# 1_1_0_Interface_board.net
KiCad netlist of a schematic drawn in Altium Designer
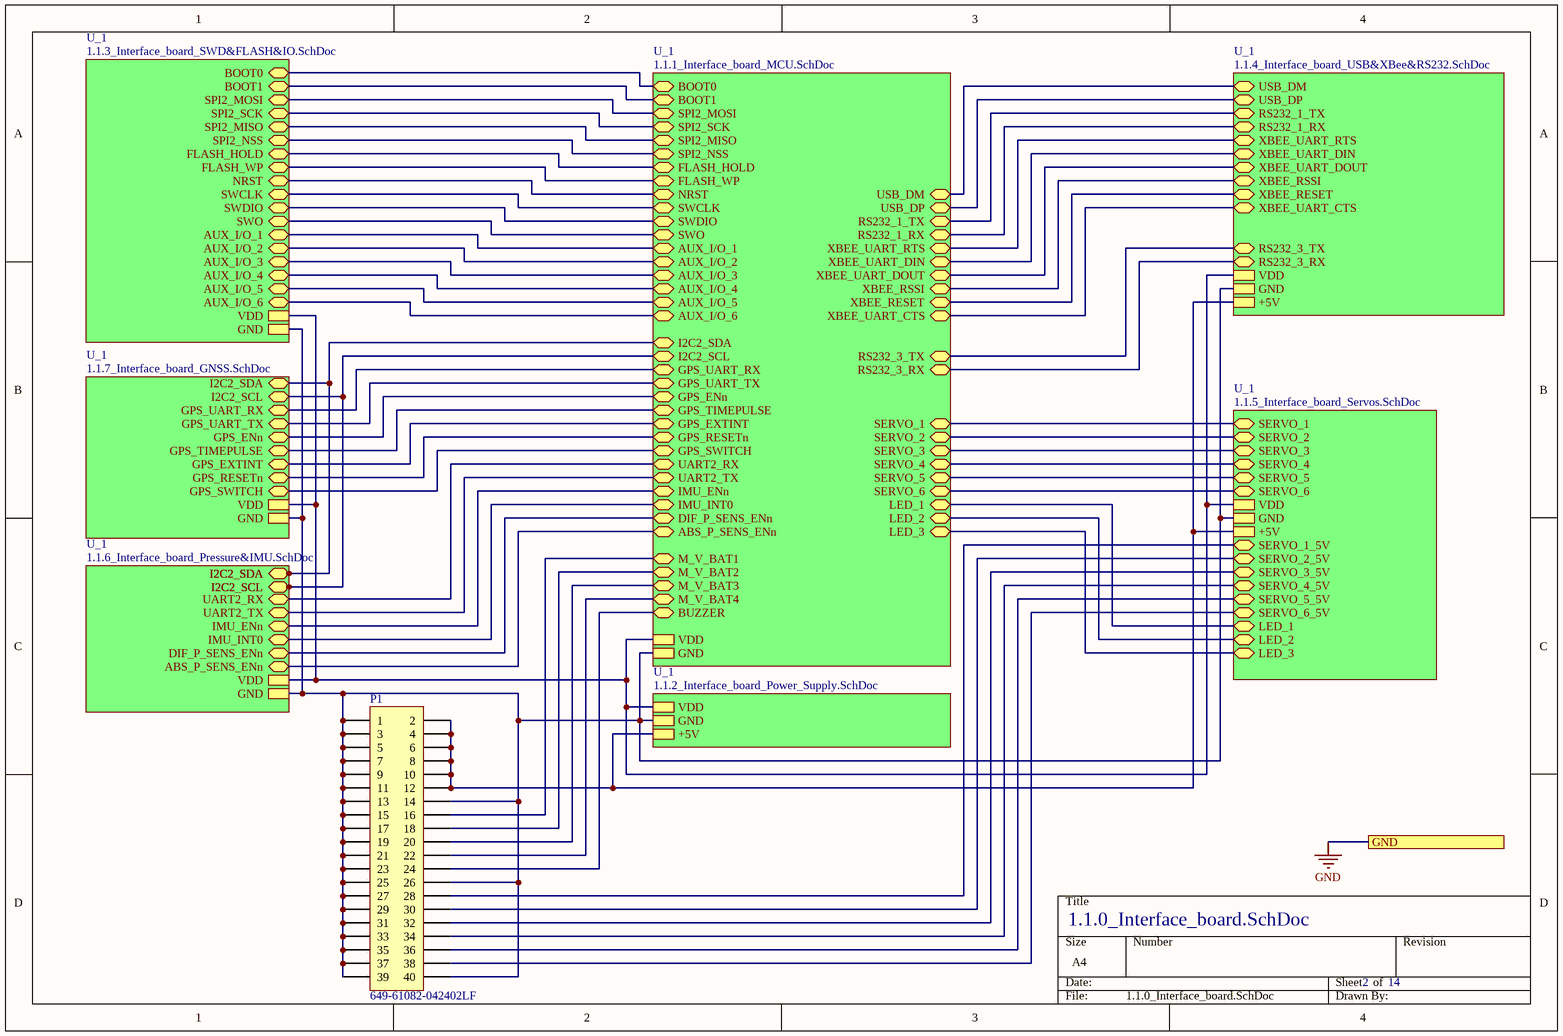
[diagram p0: 1.1.0_Interface_board.SchDoc]

(export (version "E")
  (design (tool "Eeschema 10.0.6"))
  (components
    (comp (ref "P1")
      (value "61082-042402LF")
      (footprint "61082-042402LF")
      (description "Connecteurs carte à carte et mezzanine 40P RECPT")
      (fields (field (name "SUPPLIER PART NUMBER 1") "649-61082-042402LF"))
      (libsource (lib "Rocket_library") (part "61082-042402LF"))
    )
  )
  (nets
    (net (code "1") (name "/+5V") (class "Default")
      (node (ref "P1") (pin "10") (pinfunction "10_10") (pintype "passive"))
      (node (ref "P1") (pin "12") (pinfunction "12_12") (pintype "passive"))
      (node (ref "P1") (pin "2") (pinfunction "2_2") (pintype "passive"))
      (node (ref "P1") (pin "4") (pinfunction "4_4") (pintype "passive"))
      (node (ref "P1") (pin "6") (pinfunction "6_6") (pintype "passive"))
      (node (ref "P1") (pin "8") (pinfunction "8_8") (pintype "passive"))
    )
    (net (code "11") (name "/BUZZER") (class "Default")
      (node (ref "P1") (pin "24") (pinfunction "24_24") (pintype "passive"))
    )
    (net (code "15") (name "/GND") (class "Default")
      (node (ref "P1") (pin "1") (pinfunction "1_1") (pintype "passive"))
      (node (ref "P1") (pin "11") (pinfunction "11_11") (pintype "passive"))
      (node (ref "P1") (pin "13") (pinfunction "13_13") (pintype "passive"))
      (node (ref "P1") (pin "14") (pinfunction "14_14") (pintype "passive"))
      (node (ref "P1") (pin "15") (pinfunction "15_15") (pintype "passive"))
      (node (ref "P1") (pin "17") (pinfunction "17_17") (pintype "passive"))
      (node (ref "P1") (pin "19") (pinfunction "19_19") (pintype "passive"))
      (node (ref "P1") (pin "21") (pinfunction "21_21") (pintype "passive"))
      (node (ref "P1") (pin "23") (pinfunction "23_23") (pintype "passive"))
      (node (ref "P1") (pin "25") (pinfunction "25_25") (pintype "passive"))
      (node (ref "P1") (pin "26") (pinfunction "26_26") (pintype "passive"))
      (node (ref "P1") (pin "27") (pinfunction "27_27") (pintype "passive"))
      (node (ref "P1") (pin "29") (pinfunction "29_29") (pintype "passive"))
      (node (ref "P1") (pin "3") (pinfunction "3_3") (pintype "passive"))
      (node (ref "P1") (pin "31") (pinfunction "31_31") (pintype "passive"))
      (node (ref "P1") (pin "33") (pinfunction "33_33") (pintype "passive"))
      (node (ref "P1") (pin "35") (pinfunction "35_35") (pintype "passive"))
      (node (ref "P1") (pin "37") (pinfunction "37_37") (pintype "passive"))
      (node (ref "P1") (pin "39") (pinfunction "39_39") (pintype "passive"))
      (node (ref "P1") (pin "40") (pinfunction "40_40") (pintype "passive"))
      (node (ref "P1") (pin "5") (pinfunction "5_5") (pintype "passive"))
      (node (ref "P1") (pin "7") (pinfunction "7_7") (pintype "passive"))
      (node (ref "P1") (pin "9") (pinfunction "9_9") (pintype "passive"))
    )
    (net (code "30") (name "/M_V_BAT1") (class "Default")
      (node (ref "P1") (pin "16") (pinfunction "16_16") (pintype "passive"))
    )
    (net (code "31") (name "/M_V_BAT2") (class "Default")
      (node (ref "P1") (pin "18") (pinfunction "18_18") (pintype "passive"))
    )
    (net (code "32") (name "/M_V_BAT3") (class "Default")
      (node (ref "P1") (pin "20") (pinfunction "20_20") (pintype "passive"))
    )
    (net (code "33") (name "/M_V_BAT4") (class "Default")
      (node (ref "P1") (pin "22") (pinfunction "22_22") (pintype "passive"))
    )
    (net (code "40") (name "/SERVO_1_5V") (class "Default")
      (node (ref "P1") (pin "28") (pinfunction "28_28") (pintype "passive"))
    )
    (net (code "42") (name "/SERVO_2_5V") (class "Default")
      (node (ref "P1") (pin "30") (pinfunction "30_30") (pintype "passive"))
    )
    (net (code "44") (name "/SERVO_3_5V") (class "Default")
      (node (ref "P1") (pin "32") (pinfunction "32_32") (pintype "passive"))
    )
    (net (code "46") (name "/SERVO_4_5V") (class "Default")
      (node (ref "P1") (pin "34") (pinfunction "34_34") (pintype "passive"))
    )
    (net (code "48") (name "/SERVO_5_5V") (class "Default")
      (node (ref "P1") (pin "36") (pinfunction "36_36") (pintype "passive"))
    )
    (net (code "50") (name "/SERVO_6_5V") (class "Default")
      (node (ref "P1") (pin "38") (pinfunction "38_38") (pintype "passive"))
    )
  )
)
